# SCH-MAKEY_MAKEY_PTITTEAM_161005.net
KiCad netlist of a schematic drawn in Altium Designer
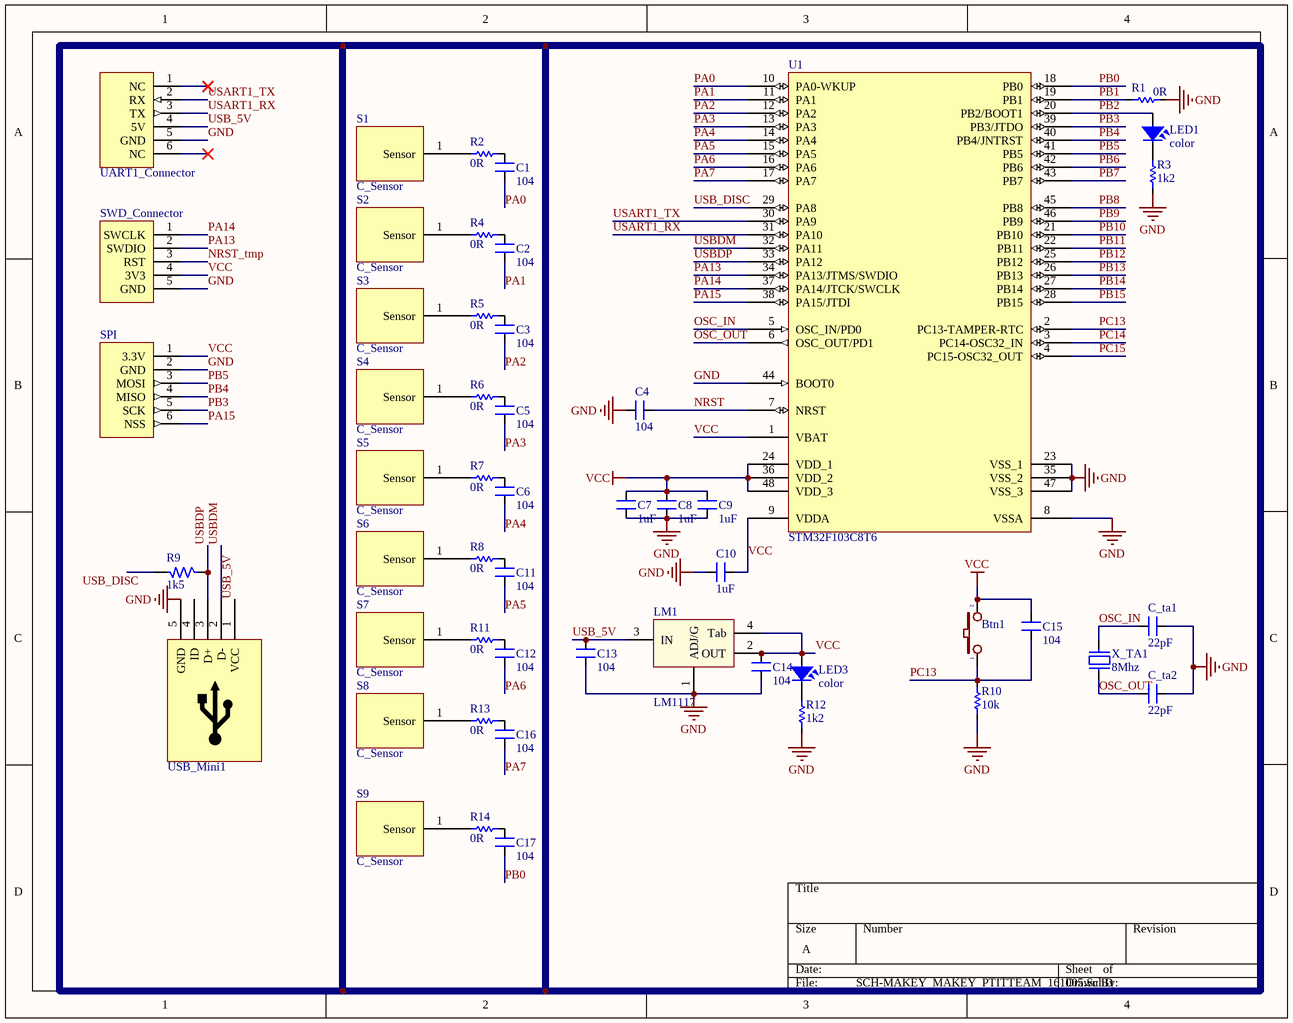
[diagram p0: SCH-MAKEY_MAKEY_PTITTEAM_161005.SchDoc]

(export (version "E")
  (design (tool "Eeschema 10.0.6"))
  (components
    (comp (ref "Btn1")
      (value "Function")
      (footprint "Button_SMD_2pin")
      (description "Switch button 2 pin")
      (libsource (lib "ptit_team_lib") (part "Button_SMD_2pin"))
    )
    (comp (ref "C1")
      (value "104")
      (footprint "CAP-0603")
      (description "Cap SMD")
      (libsource (lib "syhaunguyen") (part "CM"))
    )
    (comp (ref "C2")
      (value "104")
      (footprint "CAP-0603")
      (description "Cap SMD")
      (libsource (lib "syhaunguyen") (part "CM"))
    )
    (comp (ref "C3")
      (value "104")
      (footprint "CAP-0603")
      (description "Cap SMD")
      (libsource (lib "syhaunguyen") (part "CM"))
    )
    (comp (ref "C4")
      (value "104")
      (footprint "CAP-0603")
      (description "Cap SMD")
      (libsource (lib "syhaunguyen") (part "CM"))
    )
    (comp (ref "C5")
      (value "104")
      (footprint "CAP-0603")
      (description "Cap SMD")
      (libsource (lib "syhaunguyen") (part "CM"))
    )
    (comp (ref "C6")
      (value "104")
      (footprint "CAP-0603")
      (description "Cap SMD")
      (libsource (lib "syhaunguyen") (part "CM"))
    )
    (comp (ref "C7")
      (value "1uF")
      (footprint "CAP-0603")
      (description "Cremic For Xtal 1pF => 100pF")
      (libsource (lib "syhaunguyen") (part "CN0"))
    )
    (comp (ref "C8")
      (value "1uF")
      (footprint "CAP-0603")
      (description "Cremic For Xtal 1pF => 100pF")
      (libsource (lib "syhaunguyen") (part "CN0"))
    )
    (comp (ref "C9")
      (value "1uF")
      (footprint "CAP-0603")
      (description "Cap SMD")
      (libsource (lib "syhaunguyen") (part "CM"))
    )
    (comp (ref "C10")
      (value "1uF")
      (footprint "CAP-0603")
      (description "Cap SMD")
      (libsource (lib "syhaunguyen") (part "CM"))
    )
    (comp (ref "C11")
      (value "104")
      (footprint "CAP-0603")
      (description "Cap SMD")
      (libsource (lib "syhaunguyen") (part "CM"))
    )
    (comp (ref "C12")
      (value "104")
      (footprint "CAP-0603")
      (description "Cremic For Xtal 1pF => 100pF")
      (libsource (lib "syhaunguyen") (part "CN0"))
    )
    (comp (ref "C13")
      (value "104")
      (footprint "CAP-0603")
      (description "Cap SMD")
      (libsource (lib "syhaunguyen") (part "CM"))
    )
    (comp (ref "C14")
      (value "104")
      (footprint "CAP-0603")
      (description "Cap SMD")
      (libsource (lib "syhaunguyen") (part "CM"))
    )
    (comp (ref "C15")
      (value "104")
      (footprint "CAP-0603")
      (description "Cap SMD")
      (libsource (lib "syhaunguyen") (part "CM"))
    )
    (comp (ref "C16")
      (value "104")
      (footprint "CAP-0603")
      (description "Cremic For Xtal 1pF => 100pF")
      (libsource (lib "syhaunguyen") (part "CN0"))
    )
    (comp (ref "C17")
      (value "104")
      (footprint "CAP-0603")
      (description "Cremic For Xtal 1pF => 100pF")
      (libsource (lib "syhaunguyen") (part "CN0"))
    )
    (comp (ref "C_ta1")
      (value "22pF")
      (footprint "CAP-0603")
      (description "Cremic For Xtal 1pF => 100pF")
      (libsource (lib "syhaunguyen") (part "CN0"))
    )
    (comp (ref "C_ta2")
      (value "22pF")
      (footprint "CAP-0603")
      (description "Cremic For Xtal 1pF => 100pF")
      (libsource (lib "syhaunguyen") (part "CN0"))
    )
    (comp (ref "LED1")
      (value "color")
      (footprint "LED-0805")
      (description "Led smd")
      (libsource (lib "ptit_team_lib") (part "Led_SMD"))
    )
    (comp (ref "LED3")
      (value "color")
      (footprint "LED-0805")
      (description "Led smd")
      (libsource (lib "ptit_team_lib") (part "Led_SMD"))
    )
    (comp (ref "LM1")
      (value "LM1117")
      (footprint "SOT223-4N")
      (description "3v3")
      (libsource (lib "syhaunguyen") (part "LM1117"))
    )
    (comp (ref "R1")
      (value "0R")
      (footprint "RES-0603")
      (description "Resistor smd 0603 type")
      (libsource (lib "ptit_team_lib") (part "Res_SMD_0603"))
    )
    (comp (ref "R2")
      (value "0R")
      (footprint "RES-0603")
      (description "Resistor smd 0603 type")
      (libsource (lib "ptit_team_lib") (part "Res_SMD_0603"))
    )
    (comp (ref "R3")
      (value "1k2")
      (footprint "RES-0603")
      (description "Resistor smd 0603 type")
      (libsource (lib "ptit_team_lib") (part "Res_SMD_0603"))
    )
    (comp (ref "R4")
      (value "0R")
      (footprint "RES-0603")
      (description "Resistor smd 0603 type")
      (libsource (lib "ptit_team_lib") (part "Res_SMD_0603"))
    )
    (comp (ref "R5")
      (value "0R")
      (footprint "RES-0603")
      (description "Resistor smd 0603 type")
      (libsource (lib "ptit_team_lib") (part "Res_SMD_0603"))
    )
    (comp (ref "R6")
      (value "0R")
      (footprint "RES-0603")
      (description "Resistor smd 0603 type")
      (libsource (lib "ptit_team_lib") (part "Res_SMD_0603"))
    )
    (comp (ref "R7")
      (value "0R")
      (footprint "RES-0603")
      (description "Resistor smd 0603 type")
      (libsource (lib "ptit_team_lib") (part "Res_SMD_0603"))
    )
    (comp (ref "R8")
      (value "0R")
      (footprint "RES-0603")
      (description "Resistor smd 0603 type")
      (libsource (lib "ptit_team_lib") (part "Res_SMD_0603"))
    )
    (comp (ref "R9")
      (value "1k5")
      (footprint "RES-0603")
      (description "Resistor 1/4W")
      (libsource (lib "syhaunguyen") (part "R"))
    )
    (comp (ref "R10")
      (value "10k")
      (footprint "RES-0603")
      (description "Resistor smd 0603 type")
      (libsource (lib "ptit_team_lib") (part "Res_SMD_0603"))
    )
    (comp (ref "R11")
      (value "0R")
      (footprint "RES-0603")
      (description "Resistor smd 0603 type")
      (libsource (lib "ptit_team_lib") (part "Res_SMD_0603"))
    )
    (comp (ref "R12")
      (value "1k2")
      (footprint "RES-0603")
      (description "Resistor smd 0603 type")
      (libsource (lib "ptit_team_lib") (part "Res_SMD_0603"))
    )
    (comp (ref "R13")
      (value "0R")
      (footprint "RES-0603")
      (description "Resistor smd 0603 type")
      (libsource (lib "ptit_team_lib") (part "Res_SMD_0603"))
    )
    (comp (ref "R14")
      (value "0R")
      (footprint "RES-0603")
      (description "Resistor smd 0603 type")
      (libsource (lib "ptit_team_lib") (part "Res_SMD_0603"))
    )
    (comp (ref "S1") (value "C_Sensor") (footprint "SOP2") (libsource (lib "C_sensor") (part "C_Sensor")))
    (comp (ref "S2") (value "C_Sensor") (footprint "SOP2") (libsource (lib "C_sensor") (part "C_Sensor")))
    (comp (ref "S3") (value "C_Sensor") (footprint "SOP2") (libsource (lib "C_sensor") (part "C_Sensor")))
    (comp (ref "S4") (value "C_Sensor") (footprint "SOP2") (libsource (lib "C_sensor") (part "C_Sensor")))
    (comp (ref "S5") (value "C_Sensor") (footprint "SOP2") (libsource (lib "C_sensor") (part "C_Sensor")))
    (comp (ref "S6") (value "C_Sensor") (footprint "SOP2") (libsource (lib "C_sensor") (part "C_Sensor")))
    (comp (ref "S7") (value "C_Sensor") (footprint "SOP2") (libsource (lib "C_sensor") (part "C_Sensor")))
    (comp (ref "S8") (value "C_Sensor") (footprint "SOP2") (libsource (lib "C_sensor") (part "C_Sensor")))
    (comp (ref "S9") (value "C_Sensor") (footprint "SOP2") (libsource (lib "C_sensor") (part "C_Sensor")))
    (comp (ref "SPI") (value "~") (footprint "JP6") (libsource (lib "ptit_team_lib") (part "SPI_Connector")))
    (comp (ref "SWD_Connector")
      (value "~")
      (footprint "JP_5")
      (libsource (lib "ptit_team_lib") (part "Load_Program"))
    )
    (comp (ref "U1")
      (value "STM32F103C8T6")
      (footprint "LQFP48_N")
      (description "STM32 ARM-based 32-bit MCU with 64 Kbytes Flash, 48-pin LQFP, Industrial Temperature")
      (fields (field (name "PUBLISHER") "Altium Limited"))
      (libsource (lib "STM32F103C8T6") (part "STM32F103C8T6"))
    )
    (comp (ref "UART1_Connector")
      (value "Connector")
      (footprint "JP6")
      (description "Connector to USB2Com module")
      (libsource (lib "ptit_team_lib") (part "USB2Com_Conn"))
    )
    (comp (ref "USB_Mini1") (value "~") (footprint "Micro_USB") (libsource (lib "ARM") (part "USB_M")))
    (comp (ref "X_TA1")
      (value "8Mhz")
      (footprint "XT2")
      (description "Crystal For all Crystal 2pin.")
      (libsource (lib "syhaunguyen") (part "XT2"))
    )
  )
  (nets
    (net (code "1") (name "/NRST") (class "Default")
      (node (ref "C4") (pin "1") (pinfunction "1_1") (pintype "passive"))
      (node (ref "U1") (pin "7") (pinfunction "NRST_7") (pintype "bidirectional"))
    )
    (net (code "2") (name "/NRST_tmp") (class "Default")
      (node (ref "SWD_Connector") (pin "3") (pinfunction "RST_3") (pintype "open_emitter"))
    )
    (net (code "3") (name "/OSC_IN") (class "Default")
      (node (ref "C_ta1") (pin "1") (pinfunction "1_1") (pintype "passive"))
      (node (ref "U1") (pin "5") (pinfunction "OSC_IN/PD0_5") (pintype "input"))
      (node (ref "X_TA1") (pin "2") (pinfunction "2_2") (pintype "passive"))
    )
    (net (code "4") (name "/OSC_OUT") (class "Default")
      (node (ref "C_ta2") (pin "1") (pinfunction "1_1") (pintype "passive"))
      (node (ref "U1") (pin "6") (pinfunction "OSC_OUT/PD1_6") (pintype "output"))
      (node (ref "X_TA1") (pin "1") (pinfunction "1_1") (pintype "passive"))
    )
    (net (code "5") (name "/PA0") (class "Default")
      (node (ref "C1") (pin "1") (pinfunction "1_1") (pintype "passive"))
      (node (ref "U1") (pin "10") (pinfunction "PA0-WKUP_10") (pintype "bidirectional"))
    )
    (net (code "6") (name "/PA1") (class "Default")
      (node (ref "C2") (pin "1") (pinfunction "1_1") (pintype "passive"))
      (node (ref "U1") (pin "11") (pinfunction "PA1_11") (pintype "bidirectional"))
    )
    (net (code "7") (name "/PA2") (class "Default")
      (node (ref "C3") (pin "1") (pinfunction "1_1") (pintype "passive"))
      (node (ref "U1") (pin "12") (pinfunction "PA2_12") (pintype "bidirectional"))
    )
    (net (code "8") (name "/PA3") (class "Default")
      (node (ref "C5") (pin "1") (pinfunction "1_1") (pintype "passive"))
      (node (ref "U1") (pin "13") (pinfunction "PA3_13") (pintype "bidirectional"))
    )
    (net (code "9") (name "/PA4") (class "Default")
      (node (ref "C6") (pin "1") (pinfunction "1_1") (pintype "passive"))
      (node (ref "U1") (pin "14") (pinfunction "PA4_14") (pintype "bidirectional"))
    )
    (net (code "10") (name "/PA5") (class "Default")
      (node (ref "C11") (pin "1") (pinfunction "1_1") (pintype "passive"))
      (node (ref "U1") (pin "15") (pinfunction "PA5_15") (pintype "bidirectional"))
    )
    (net (code "11") (name "/PA6") (class "Default")
      (node (ref "C12") (pin "1") (pinfunction "1_1") (pintype "passive"))
      (node (ref "U1") (pin "16") (pinfunction "PA6_16") (pintype "bidirectional"))
    )
    (net (code "12") (name "/PA7") (class "Default")
      (node (ref "C16") (pin "1") (pinfunction "1_1") (pintype "passive"))
      (node (ref "U1") (pin "17") (pinfunction "PA7_17") (pintype "bidirectional"))
    )
    (net (code "13") (name "/PA13") (class "Default")
      (node (ref "SWD_Connector") (pin "2") (pinfunction "SWDIO_2") (pintype "open_emitter"))
      (node (ref "U1") (pin "34") (pinfunction "PA13/JTMS/SWDIO_34") (pintype "bidirectional"))
    )
    (net (code "14") (name "/PA14") (class "Default")
      (node (ref "SWD_Connector") (pin "1") (pinfunction "SWCLK_1") (pintype "open_emitter"))
      (node (ref "U1") (pin "37") (pinfunction "PA14/JTCK/SWCLK_37") (pintype "bidirectional"))
    )
    (net (code "15") (name "/PA15") (class "Default")
      (node (ref "SPI") (pin "6") (pinfunction "NSS_6") (pintype "output"))
      (node (ref "U1") (pin "38") (pinfunction "PA15/JTDI_38") (pintype "bidirectional"))
    )
    (net (code "16") (name "/PB0") (class "Default")
      (node (ref "C17") (pin "1") (pinfunction "1_1") (pintype "passive"))
      (node (ref "U1") (pin "18") (pinfunction "PB0_18") (pintype "bidirectional"))
    )
    (net (code "17") (name "/PB1") (class "Default")
      (node (ref "R1") (pin "2") (pinfunction "2_2") (pintype "passive"))
      (node (ref "U1") (pin "19") (pinfunction "PB1_19") (pintype "bidirectional"))
    )
    (net (code "18") (name "/PB2") (class "Default")
      (node (ref "LED1") (pin "1") (pinfunction "1_1") (pintype "passive"))
      (node (ref "U1") (pin "20") (pinfunction "PB2/BOOT1_20") (pintype "bidirectional"))
    )
    (net (code "19") (name "/PB3") (class "Default")
      (node (ref "SPI") (pin "5") (pinfunction "SCK_5") (pintype "output"))
      (node (ref "U1") (pin "39") (pinfunction "PB3/JTDO_39") (pintype "bidirectional"))
    )
    (net (code "20") (name "/PB4") (class "Default")
      (node (ref "SPI") (pin "4") (pinfunction "MISO_4") (pintype "output"))
      (node (ref "U1") (pin "40") (pinfunction "PB4/JNTRST_40") (pintype "bidirectional"))
    )
    (net (code "21") (name "/PB5") (class "Default")
      (node (ref "SPI") (pin "3") (pinfunction "MOSI_3") (pintype "output"))
      (node (ref "U1") (pin "41") (pinfunction "PB5_41") (pintype "bidirectional"))
    )
    (net (code "22") (name "/PB6") (class "Default")
      (node (ref "U1") (pin "42") (pinfunction "PB6_42") (pintype "bidirectional"))
    )
    (net (code "23") (name "/PB7") (class "Default")
      (node (ref "U1") (pin "43") (pinfunction "PB7_43") (pintype "bidirectional"))
    )
    (net (code "24") (name "/PB8") (class "Default")
      (node (ref "U1") (pin "45") (pinfunction "PB8_45") (pintype "bidirectional"))
    )
    (net (code "25") (name "/PB9") (class "Default")
      (node (ref "U1") (pin "46") (pinfunction "PB9_46") (pintype "bidirectional"))
    )
    (net (code "26") (name "/PB10") (class "Default")
      (node (ref "U1") (pin "21") (pinfunction "PB10_21") (pintype "bidirectional"))
    )
    (net (code "27") (name "/PB11") (class "Default")
      (node (ref "U1") (pin "22") (pinfunction "PB11_22") (pintype "bidirectional"))
    )
    (net (code "28") (name "/PB12") (class "Default")
      (node (ref "U1") (pin "25") (pinfunction "PB12_25") (pintype "bidirectional"))
    )
    (net (code "29") (name "/PB13") (class "Default")
      (node (ref "U1") (pin "26") (pinfunction "PB13_26") (pintype "bidirectional"))
    )
    (net (code "30") (name "/PB14") (class "Default")
      (node (ref "U1") (pin "27") (pinfunction "PB14_27") (pintype "bidirectional"))
    )
    (net (code "31") (name "/PB15") (class "Default")
      (node (ref "U1") (pin "28") (pinfunction "PB15_28") (pintype "bidirectional"))
    )
    (net (code "32") (name "/PC13") (class "Default")
      (node (ref "Btn1") (pin "1") (pinfunction "1_1") (pintype "passive"))
      (node (ref "C15") (pin "1") (pinfunction "1_1") (pintype "passive"))
      (node (ref "R10") (pin "2") (pinfunction "2_2") (pintype "passive"))
      (node (ref "U1") (pin "2") (pinfunction "PC13-TAMPER-RTC_2") (pintype "bidirectional"))
    )
    (net (code "33") (name "/PC14") (class "Default")
      (node (ref "U1") (pin "3") (pinfunction "PC14-OSC32_IN_3") (pintype "bidirectional"))
    )
    (net (code "34") (name "/PC15") (class "Default")
      (node (ref "U1") (pin "4") (pinfunction "PC15-OSC32_OUT_4") (pintype "bidirectional"))
    )
    (net (code "35") (name "/USART1_RX") (class "Default")
      (node (ref "U1") (pin "31") (pinfunction "PA10_31") (pintype "bidirectional"))
      (node (ref "UART1_Connector") (pin "3") (pinfunction "TX_3") (pintype "output"))
    )
    (net (code "36") (name "/USART1_TX") (class "Default")
      (node (ref "U1") (pin "30") (pinfunction "PA9_30") (pintype "bidirectional"))
      (node (ref "UART1_Connector") (pin "2") (pinfunction "RX_2") (pintype "input"))
    )
    (net (code "37") (name "/USBDM") (class "Default")
      (node (ref "U1") (pin "32") (pinfunction "PA11_32") (pintype "bidirectional"))
      (node (ref "USB_Mini1") (pin "2") (pinfunction "D-_2") (pintype "passive"))
    )
    (net (code "38") (name "/USBDP") (class "Default")
      (node (ref "R9") (pin "1") (pinfunction "1_1") (pintype "passive"))
      (node (ref "U1") (pin "33") (pinfunction "PA12_33") (pintype "bidirectional"))
      (node (ref "USB_Mini1") (pin "3") (pinfunction "D+_3") (pintype "passive"))
    )
    (net (code "39") (name "/USB_5V") (class "Default")
      (node (ref "C13") (pin "2") (pinfunction "2_2") (pintype "passive"))
      (node (ref "LM1") (pin "3") (pinfunction "IN_3") (pintype "passive"))
      (node (ref "UART1_Connector") (pin "4") (pinfunction "5V_4") (pintype "power_in"))
      (node (ref "USB_Mini1") (pin "1") (pinfunction "VCC_1") (pintype "passive"))
    )
    (net (code "40") (name "/USB_DISC") (class "Default")
      (node (ref "R9") (pin "2") (pinfunction "2_2") (pintype "passive"))
      (node (ref "U1") (pin "29") (pinfunction "PA8_29") (pintype "bidirectional"))
    )
    (net (code "41") (name "GND") (class "Default")
      (node (ref "C10") (pin "2") (pinfunction "2_2") (pintype "passive"))
      (node (ref "C13") (pin "1") (pinfunction "1_1") (pintype "passive"))
      (node (ref "C14") (pin "1") (pinfunction "1_1") (pintype "passive"))
      (node (ref "C4") (pin "2") (pinfunction "2_2") (pintype "passive"))
      (node (ref "C7") (pin "1") (pinfunction "1_1") (pintype "passive"))
      (node (ref "C8") (pin "2") (pinfunction "2_2") (pintype "passive"))
      (node (ref "C9") (pin "1") (pinfunction "1_1") (pintype "passive"))
      (node (ref "C_ta1") (pin "2") (pinfunction "2_2") (pintype "passive"))
      (node (ref "C_ta2") (pin "2") (pinfunction "2_2") (pintype "passive"))
      (node (ref "LM1") (pin "1") (pinfunction "ADJ/G_1") (pintype "passive"))
      (node (ref "R1") (pin "1") (pinfunction "1_1") (pintype "passive"))
      (node (ref "R10") (pin "1") (pinfunction "1_1") (pintype "passive"))
      (node (ref "R12") (pin "1") (pinfunction "1_1") (pintype "passive"))
      (node (ref "R3") (pin "1") (pinfunction "1_1") (pintype "passive"))
      (node (ref "SPI") (pin "2") (pinfunction "GND_2") (pintype "power_in"))
      (node (ref "SWD_Connector") (pin "5") (pinfunction "GND_5") (pintype "power_in"))
      (node (ref "U1") (pin "23") (pinfunction "VSS_1_23") (pintype "power_in"))
      (node (ref "U1") (pin "35") (pinfunction "VSS_2_35") (pintype "power_in"))
      (node (ref "U1") (pin "44") (pinfunction "BOOT0_44") (pintype "input"))
      (node (ref "U1") (pin "47") (pinfunction "VSS_3_47") (pintype "power_in"))
      (node (ref "U1") (pin "8") (pinfunction "VSSA_8") (pintype "power_in"))
      (node (ref "UART1_Connector") (pin "5") (pinfunction "GND_5") (pintype "power_in"))
      (node (ref "USB_Mini1") (pin "5") (pinfunction "GND_5") (pintype "passive"))
    )
    (net (code "42") (name "Net-(C1-Pad2)") (class "Default")
      (node (ref "C1") (pin "2") (pinfunction "2_2") (pintype "passive"))
      (node (ref "R2") (pin "1") (pinfunction "1_1") (pintype "passive"))
    )
    (net (code "43") (name "Net-(C2-Pad2)") (class "Default")
      (node (ref "C2") (pin "2") (pinfunction "2_2") (pintype "passive"))
      (node (ref "R4") (pin "1") (pinfunction "1_1") (pintype "passive"))
    )
    (net (code "44") (name "Net-(C3-Pad2)") (class "Default")
      (node (ref "C3") (pin "2") (pinfunction "2_2") (pintype "passive"))
      (node (ref "R5") (pin "1") (pinfunction "1_1") (pintype "passive"))
    )
    (net (code "45") (name "Net-(C5-Pad2)") (class "Default")
      (node (ref "C5") (pin "2") (pinfunction "2_2") (pintype "passive"))
      (node (ref "R6") (pin "1") (pinfunction "1_1") (pintype "passive"))
    )
    (net (code "46") (name "Net-(C6-Pad2)") (class "Default")
      (node (ref "C6") (pin "2") (pinfunction "2_2") (pintype "passive"))
      (node (ref "R7") (pin "1") (pinfunction "1_1") (pintype "passive"))
    )
    (net (code "47") (name "Net-(C11-Pad2)") (class "Default")
      (node (ref "C11") (pin "2") (pinfunction "2_2") (pintype "passive"))
      (node (ref "R8") (pin "1") (pinfunction "1_1") (pintype "passive"))
    )
    (net (code "48") (name "Net-(C12-Pad2)") (class "Default")
      (node (ref "C12") (pin "2") (pinfunction "2_2") (pintype "passive"))
      (node (ref "R11") (pin "1") (pinfunction "1_1") (pintype "passive"))
    )
    (net (code "49") (name "Net-(C16-Pad2)") (class "Default")
      (node (ref "C16") (pin "2") (pinfunction "2_2") (pintype "passive"))
      (node (ref "R13") (pin "1") (pinfunction "1_1") (pintype "passive"))
    )
    (net (code "50") (name "Net-(C17-Pad2)") (class "Default")
      (node (ref "C17") (pin "2") (pinfunction "2_2") (pintype "passive"))
      (node (ref "R14") (pin "1") (pinfunction "1_1") (pintype "passive"))
    )
    (net (code "51") (name "Net-(LED1-Pad2)") (class "Default")
      (node (ref "LED1") (pin "2") (pinfunction "2_2") (pintype "passive"))
      (node (ref "R3") (pin "2") (pinfunction "2_2") (pintype "passive"))
    )
    (net (code "52") (name "Net-(LED3-Pad2)") (class "Default")
      (node (ref "LED3") (pin "2") (pinfunction "2_2") (pintype "passive"))
      (node (ref "R12") (pin "2") (pinfunction "2_2") (pintype "passive"))
    )
    (net (code "53") (name "Net-(S1-Sensor)") (class "Default")
      (node (ref "R2") (pin "2") (pinfunction "2_2") (pintype "passive"))
      (node (ref "S1") (pin "1") (pinfunction "Sensor_1") (pintype "passive"))
    )
    (net (code "54") (name "Net-(S2-Sensor)") (class "Default")
      (node (ref "R4") (pin "2") (pinfunction "2_2") (pintype "passive"))
      (node (ref "S2") (pin "1") (pinfunction "Sensor_1") (pintype "passive"))
    )
    (net (code "55") (name "Net-(S3-Sensor)") (class "Default")
      (node (ref "R5") (pin "2") (pinfunction "2_2") (pintype "passive"))
      (node (ref "S3") (pin "1") (pinfunction "Sensor_1") (pintype "passive"))
    )
    (net (code "56") (name "Net-(S4-Sensor)") (class "Default")
      (node (ref "R6") (pin "2") (pinfunction "2_2") (pintype "passive"))
      (node (ref "S4") (pin "1") (pinfunction "Sensor_1") (pintype "passive"))
    )
    (net (code "57") (name "Net-(S5-Sensor)") (class "Default")
      (node (ref "R7") (pin "2") (pinfunction "2_2") (pintype "passive"))
      (node (ref "S5") (pin "1") (pinfunction "Sensor_1") (pintype "passive"))
    )
    (net (code "58") (name "Net-(S6-Sensor)") (class "Default")
      (node (ref "R8") (pin "2") (pinfunction "2_2") (pintype "passive"))
      (node (ref "S6") (pin "1") (pinfunction "Sensor_1") (pintype "passive"))
    )
    (net (code "59") (name "Net-(S7-Sensor)") (class "Default")
      (node (ref "R11") (pin "2") (pinfunction "2_2") (pintype "passive"))
      (node (ref "S7") (pin "1") (pinfunction "Sensor_1") (pintype "passive"))
    )
    (net (code "60") (name "Net-(S8-Sensor)") (class "Default")
      (node (ref "R13") (pin "2") (pinfunction "2_2") (pintype "passive"))
      (node (ref "S8") (pin "1") (pinfunction "Sensor_1") (pintype "passive"))
    )
    (net (code "61") (name "Net-(S9-Sensor)") (class "Default")
      (node (ref "R14") (pin "2") (pinfunction "2_2") (pintype "passive"))
      (node (ref "S9") (pin "1") (pinfunction "Sensor_1") (pintype "passive"))
    )
    (net (code "62") (name "VCC") (class "Default")
      (node (ref "Btn1") (pin "2") (pinfunction "2_2") (pintype "passive"))
      (node (ref "C10") (pin "1") (pinfunction "1_1") (pintype "passive"))
      (node (ref "C14") (pin "2") (pinfunction "2_2") (pintype "passive"))
      (node (ref "C15") (pin "2") (pinfunction "2_2") (pintype "passive"))
      (node (ref "C7") (pin "2") (pinfunction "2_2") (pintype "passive"))
      (node (ref "C8") (pin "1") (pinfunction "1_1") (pintype "passive"))
      (node (ref "C9") (pin "2") (pinfunction "2_2") (pintype "passive"))
      (node (ref "LED3") (pin "1") (pinfunction "1_1") (pintype "passive"))
      (node (ref "LM1") (pin "2") (pinfunction "OUT_2") (pintype "passive"))
      (node (ref "LM1") (pin "4") (pinfunction "Tab_4") (pintype "passive"))
      (node (ref "SPI") (pin "1") (pinfunction "3.3V_1") (pintype "open_emitter"))
      (node (ref "SWD_Connector") (pin "4") (pinfunction "3V3_4") (pintype "power_in"))
      (node (ref "U1") (pin "1") (pinfunction "VBAT_1") (pintype "power_in"))
      (node (ref "U1") (pin "24") (pinfunction "VDD_1_24") (pintype "power_in"))
      (node (ref "U1") (pin "36") (pinfunction "VDD_2_36") (pintype "power_in"))
      (node (ref "U1") (pin "48") (pinfunction "VDD_3_48") (pintype "power_in"))
      (node (ref "U1") (pin "9") (pinfunction "VDDA_9") (pintype "power_in"))
    )
    (net (code "63") (name "unconnected-(UART1_Connector-NC-Pad1)") (class "Default")
      (node (ref "UART1_Connector") (pin "1") (pinfunction "NC_1") (pintype "passive+no_connect"))
    )
    (net (code "64") (name "unconnected-(UART1_Connector-NC-Pad6)") (class "Default")
      (node (ref "UART1_Connector") (pin "6") (pinfunction "NC_6") (pintype "passive+no_connect"))
    )
    (net (code "65") (name "unconnected-(USB_Mini1-ID-Pad4)") (class "Default")
      (node (ref "USB_Mini1") (pin "4") (pinfunction "ID_4") (pintype "passive"))
    )
  )
)
